# RF_Duinode_V3.net
KiCad netlist of a schematic drawn in EAGLE
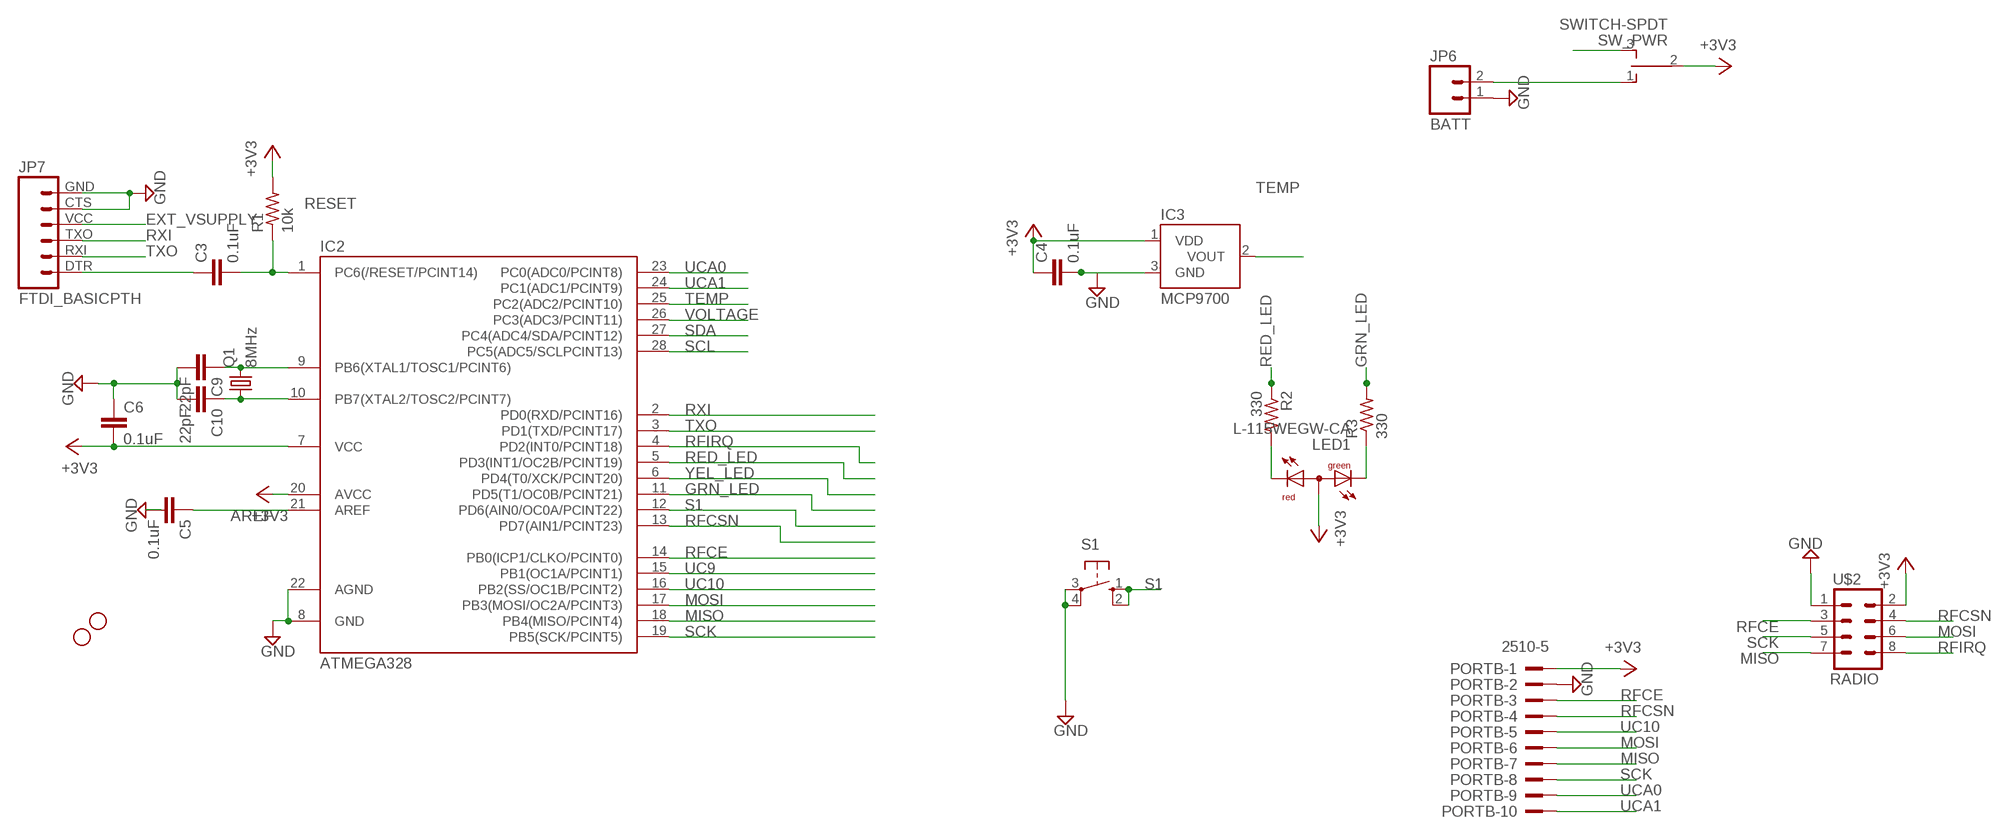
[diagram p0: schematic, sheet 1]

(export (version "E")
  (design (tool "Eeschema 10.0.6"))
  (components
    (comp (ref "C3")
      (value "0.1uF")
      (footprint "eagle-import:C025-025X050")
      (libsource (lib "eagle-import") (part "C-EU025-025X050"))
    )
    (comp (ref "C4")
      (value "0.1uF")
      (footprint "eagle-import:C025-025X050")
      (libsource (lib "eagle-import") (part "C-EU025-025X050"))
    )
    (comp (ref "C5")
      (value "0.1uF")
      (footprint "eagle-import:C025-025X050")
      (libsource (lib "eagle-import") (part "C-EU025-025X050"))
    )
    (comp (ref "C6")
      (value "0.1uF")
      (footprint "eagle-import:C025-025X050")
      (libsource (lib "eagle-import") (part "C-EU025-025X050"))
    )
    (comp (ref "C9")
      (value "22pF")
      (footprint "eagle-import:C025-025X050")
      (libsource (lib "eagle-import") (part "C-EU025-025X050"))
    )
    (comp (ref "C10")
      (value "22pF")
      (footprint "eagle-import:C025-025X050")
      (libsource (lib "eagle-import") (part "C-EU025-025X050"))
    )
    (comp (ref "IC2")
      (value "ATMEGA328")
      (footprint "eagle-import:DIL28-3")
      (libsource (lib "eagle-import") (part "ATMEGA48/88/168-PU"))
    )
    (comp (ref "IC3")
      (value "MCP9700")
      (footprint "eagle-import:TO-92")
      (libsource (lib "eagle-import") (part "MCP9700"))
    )
    (comp (ref "JP2")
      (value "STAND-OFF")
      (footprint "eagle-import:STAND-OFF")
      (libsource (lib "eagle-import") (part "STAND-OFF"))
    )
    (comp (ref "JP6")
      (value "BATT")
      (footprint "eagle-import:1X02_LOCK")
      (libsource (lib "eagle-import") (part "M02LOCK"))
    )
    (comp (ref "JP7")
      (value "FTDI_BASICPTH")
      (footprint "eagle-import:FTDI_BASIC")
      (libsource (lib "eagle-import") (part "FTDI_BASICPTH"))
    )
    (comp (ref "JP8")
      (value "STAND-OFF")
      (footprint "eagle-import:STAND-OFF")
      (libsource (lib "eagle-import") (part "STAND-OFF"))
    )
    (comp (ref "LED1")
      (value "L-115WEGW-CA")
      (footprint "eagle-import:DUOLED-A-3MM")
      (libsource (lib "eagle-import") (part "L-115WEGW-CA"))
    )
    (comp (ref "PORTB")
      (value "2510-5")
      (footprint "eagle-import:PAK100_2500-5-10")
      (libsource (lib "eagle-import") (part "2510-5"))
    )
    (comp (ref "Q1")
      (value "8MHz")
      (footprint "eagle-import:HC49_S")
      (libsource (lib "eagle-import") (part "CRYSTALHC49S"))
    )
    (comp (ref "R1")
      (value "10k")
      (footprint "eagle-import:0204V")
      (libsource (lib "eagle-import") (part "R-US_0204/2V"))
    )
    (comp (ref "R2")
      (value "330")
      (footprint "eagle-import:0204V")
      (libsource (lib "eagle-import") (part "R-US_0204/2V"))
    )
    (comp (ref "R3")
      (value "330")
      (footprint "eagle-import:0204V")
      (libsource (lib "eagle-import") (part "R-US_0204/2V"))
    )
    (comp (ref "S1")
      (value "10-XX")
      (footprint "eagle-import:B3F-10XX")
      (fields (field (name "MPN") "B3F-1000"))
      (libsource (lib "eagle-import") (part "10-XX"))
    )
    (comp (ref "SW_PWR")
      (value "SWITCH-SPDT")
      (footprint "eagle-import:OS102011MS2QN1")
      (libsource (lib "eagle-import") (part "SWITCH-SPDT"))
    )
    (comp (ref "U$2")
      (value "RADIO")
      (footprint "eagle-import:2X4")
      (libsource (lib "eagle-import") (part "M04X2"))
    )
  )
  (nets
    (net (code "1") (name "+3V3") (class "Default")
      (node (ref "C4") (pin "1") (pinfunction "1_1") (pintype "passive"))
      (node (ref "C6") (pin "2") (pinfunction "2_2") (pintype "passive"))
      (node (ref "IC2") (pin "20") (pinfunction "AVCC_20") (pintype "passive"))
      (node (ref "IC2") (pin "7") (pinfunction "VCC_7") (pintype "power_in"))
      (node (ref "IC3") (pin "1") (pinfunction "VDD_1") (pintype "bidirectional"))
      (node (ref "LED1") (pin "2") (pinfunction "A_2") (pintype "passive"))
      (node (ref "PORTB") (pin "1") (pinfunction "KL_1") (pintype "passive"))
      (node (ref "R1") (pin "2") (pinfunction "2_2") (pintype "passive"))
      (node (ref "SW_PWR") (pin "2") (pinfunction "P_2") (pintype "passive"))
      (node (ref "U$2") (pin "2") (pinfunction "2_2") (pintype "passive"))
    )
    (net (code "2") (name "/AREF") (class "Default")
      (node (ref "C5") (pin "1") (pinfunction "1_1") (pintype "passive"))
      (node (ref "IC2") (pin "21") (pinfunction "AREF_21") (pintype "passive"))
    )
    (net (code "3") (name "/EXT_VSUPPLY") (class "Default")
      (node (ref "JP7") (pin "VCC") (pinfunction "4_VCC") (pintype "passive"))
      (node (ref "SW_PWR") (pin "3") (pinfunction "S_3") (pintype "passive"))
    )
    (net (code "4") (name "/GRN_LED") (class "Default")
      (node (ref "IC2") (pin "11") (pinfunction "PD5(T1/OC0B/PCINT21)_11") (pintype "bidirectional"))
      (node (ref "R3") (pin "2") (pinfunction "2_2") (pintype "passive"))
    )
    (net (code "5") (name "/MISO") (class "Default")
      (node (ref "IC2") (pin "18") (pinfunction "PB4(MISO/PCINT4)_18") (pintype "bidirectional"))
      (node (ref "PORTB") (pin "7") (pinfunction "KL_7") (pintype "passive"))
      (node (ref "U$2") (pin "7") (pinfunction "7_7") (pintype "passive"))
    )
    (net (code "6") (name "/MOSI") (class "Default")
      (node (ref "IC2") (pin "17") (pinfunction "PB3(MOSI/OC2A/PCINT3)_17") (pintype "bidirectional"))
      (node (ref "PORTB") (pin "6") (pinfunction "KL_6") (pintype "passive"))
      (node (ref "U$2") (pin "6") (pinfunction "6_6") (pintype "passive"))
    )
    (net (code "7") (name "/RED_LED") (class "Default")
      (node (ref "IC2") (pin "5") (pinfunction "PD3(INT1/OC2B/PCINT19)_5") (pintype "bidirectional"))
      (node (ref "R2") (pin "1") (pinfunction "1_1") (pintype "passive"))
    )
    (net (code "8") (name "/RESET") (class "Default")
      (node (ref "C3") (pin "2") (pinfunction "2_2") (pintype "passive"))
      (node (ref "IC2") (pin "1") (pinfunction "PC6(/RESET/PCINT14)_1") (pintype "bidirectional"))
      (node (ref "R1") (pin "1") (pinfunction "1_1") (pintype "passive"))
    )
    (net (code "9") (name "/RFCE") (class "Default")
      (node (ref "IC2") (pin "14") (pinfunction "PB0(ICP1/CLKO/PCINT0)_14") (pintype "bidirectional"))
      (node (ref "PORTB") (pin "3") (pinfunction "KL_3") (pintype "passive"))
      (node (ref "U$2") (pin "3") (pinfunction "3_3") (pintype "passive"))
    )
    (net (code "10") (name "/RFCSN") (class "Default")
      (node (ref "IC2") (pin "13") (pinfunction "PD7(AIN1/PCINT23)_13") (pintype "bidirectional"))
      (node (ref "PORTB") (pin "4") (pinfunction "KL_4") (pintype "passive"))
      (node (ref "U$2") (pin "4") (pinfunction "4_4") (pintype "passive"))
    )
    (net (code "11") (name "/RFIRQ") (class "Default")
      (node (ref "IC2") (pin "4") (pinfunction "PD2(INT0/PCINT18)_4") (pintype "bidirectional"))
      (node (ref "U$2") (pin "8") (pinfunction "8_8") (pintype "passive"))
    )
    (net (code "12") (name "/RXI") (class "Default")
      (node (ref "IC2") (pin "2") (pinfunction "PD0(RXD/PCINT16)_2") (pintype "bidirectional"))
      (node (ref "JP7") (pin "TXO") (pinfunction "3_TXO") (pintype "passive"))
    )
    (net (code "13") (name "/S1") (class "Default")
      (node (ref "IC2") (pin "12") (pinfunction "PD6(AIN0/OC0A/PCINT22)_12") (pintype "bidirectional"))
      (node (ref "S1") (pin "1") (pinfunction "S_1") (pintype "passive"))
      (node (ref "S1") (pin "2") (pinfunction "S1_2") (pintype "passive"))
    )
    (net (code "14") (name "/SCK") (class "Default")
      (node (ref "IC2") (pin "19") (pinfunction "PB5(SCK/PCINT5)_19") (pintype "bidirectional"))
      (node (ref "PORTB") (pin "8") (pinfunction "KL_8") (pintype "passive"))
      (node (ref "U$2") (pin "5") (pinfunction "5_5") (pintype "passive"))
    )
    (net (code "15") (name "/SCL") (class "Default")
      (node (ref "IC2") (pin "28") (pinfunction "PC5(ADC5/SCLPCINT13)_28") (pintype "bidirectional"))
    )
    (net (code "16") (name "/SDA") (class "Default")
      (node (ref "IC2") (pin "27") (pinfunction "PC4(ADC4/SDA/PCINT12)_27") (pintype "bidirectional"))
    )
    (net (code "17") (name "/TEMP") (class "Default")
      (node (ref "IC2") (pin "25") (pinfunction "PC2(ADC2/PCINT10)_25") (pintype "bidirectional"))
      (node (ref "IC3") (pin "2") (pinfunction "VOUT_2") (pintype "bidirectional"))
    )
    (net (code "18") (name "/TXO") (class "Default")
      (node (ref "IC2") (pin "3") (pinfunction "PD1(TXD/PCINT17)_3") (pintype "bidirectional"))
      (node (ref "JP7") (pin "RXI") (pinfunction "2_RXI") (pintype "passive"))
    )
    (net (code "19") (name "/UC9") (class "Default")
      (node (ref "IC2") (pin "15") (pinfunction "PB1(OC1A/PCINT1)_15") (pintype "bidirectional"))
    )
    (net (code "20") (name "/UC10") (class "Default")
      (node (ref "IC2") (pin "16") (pinfunction "PB2(SS/OC1B/PCINT2)_16") (pintype "bidirectional"))
      (node (ref "PORTB") (pin "5") (pinfunction "KL_5") (pintype "passive"))
    )
    (net (code "21") (name "/UCA0") (class "Default")
      (node (ref "IC2") (pin "23") (pinfunction "PC0(ADC0/PCINT8)_23") (pintype "bidirectional"))
      (node (ref "PORTB") (pin "9") (pinfunction "KL_9") (pintype "passive"))
    )
    (net (code "22") (name "/UCA1") (class "Default")
      (node (ref "IC2") (pin "24") (pinfunction "PC1(ADC1/PCINT9)_24") (pintype "bidirectional"))
      (node (ref "PORTB") (pin "10") (pinfunction "KL_10") (pintype "passive"))
    )
    (net (code "23") (name "/VOLTAGE") (class "Default")
      (node (ref "IC2") (pin "26") (pinfunction "PC3(ADC3/PCINT11)_26") (pintype "bidirectional"))
    )
    (net (code "24") (name "/YEL_LED") (class "Default")
      (node (ref "IC2") (pin "6") (pinfunction "PD4(T0/XCK/PCINT20)_6") (pintype "bidirectional"))
    )
    (net (code "25") (name "GND") (class "Default")
      (node (ref "C10") (pin "2") (pinfunction "2_2") (pintype "passive"))
      (node (ref "C4") (pin "2") (pinfunction "2_2") (pintype "passive"))
      (node (ref "C5") (pin "2") (pinfunction "2_2") (pintype "passive"))
      (node (ref "C6") (pin "1") (pinfunction "1_1") (pintype "passive"))
      (node (ref "C9") (pin "2") (pinfunction "2_2") (pintype "passive"))
      (node (ref "IC2") (pin "22") (pinfunction "AGND_22") (pintype "power_in"))
      (node (ref "IC2") (pin "8") (pinfunction "GND_8") (pintype "power_in"))
      (node (ref "IC3") (pin "3") (pinfunction "GND_3") (pintype "bidirectional"))
      (node (ref "JP6") (pin "1") (pinfunction "1_1") (pintype "passive"))
      (node (ref "JP7") (pin "CTS") (pinfunction "5_CTS") (pintype "passive"))
      (node (ref "JP7") (pin "GND") (pinfunction "6_GND") (pintype "passive"))
      (node (ref "PORTB") (pin "2") (pinfunction "KL_2") (pintype "passive"))
      (node (ref "S1") (pin "3") (pinfunction "P_3") (pintype "passive"))
      (node (ref "S1") (pin "4") (pinfunction "P1_4") (pintype "passive"))
      (node (ref "U$2") (pin "1") (pinfunction "1_1") (pintype "passive"))
    )
    (net (code "26") (name "Net-(IC2-PB6(XTAL1{slash}TOSC1{slash}PCINT6))") (class "Default")
      (node (ref "C9") (pin "1") (pinfunction "1_1") (pintype "passive"))
      (node (ref "IC2") (pin "9") (pinfunction "PB6(XTAL1/TOSC1/PCINT6)_9") (pintype "bidirectional"))
      (node (ref "Q1") (pin "2") (pinfunction "2_2") (pintype "passive"))
    )
    (net (code "27") (name "Net-(IC2-PB7(XTAL2{slash}TOSC2{slash}PCINT7))") (class "Default")
      (node (ref "C10") (pin "1") (pinfunction "1_1") (pintype "passive"))
      (node (ref "IC2") (pin "10") (pinfunction "PB7(XTAL2/TOSC2/PCINT7)_10") (pintype "bidirectional"))
      (node (ref "Q1") (pin "1") (pinfunction "1_1") (pintype "passive"))
    )
    (net (code "28") (name "Net-(JP7-1)") (class "Default")
      (node (ref "C3") (pin "1") (pinfunction "1_1") (pintype "passive"))
      (node (ref "JP7") (pin "DTR") (pinfunction "1_DTR") (pintype "passive"))
    )
    (net (code "29") (name "Net-(LED1-CG)") (class "Default")
      (node (ref "LED1") (pin "1") (pinfunction "CG_1") (pintype "passive"))
      (node (ref "R3") (pin "1") (pinfunction "1_1") (pintype "passive"))
    )
    (net (code "30") (name "Net-(LED1-CR)") (class "Default")
      (node (ref "LED1") (pin "3") (pinfunction "CR_3") (pintype "passive"))
      (node (ref "R2") (pin "2") (pinfunction "2_2") (pintype "passive"))
    )
    (net (code "31") (name "Net-(SW_PWR-O)") (class "Default")
      (node (ref "JP6") (pin "2") (pinfunction "2_2") (pintype "passive"))
      (node (ref "SW_PWR") (pin "1") (pinfunction "O_1") (pintype "passive"))
    )
  )
)
